# WS2812B_Single_Channel.net
KiCad netlist of a schematic drawn in Altium Designer
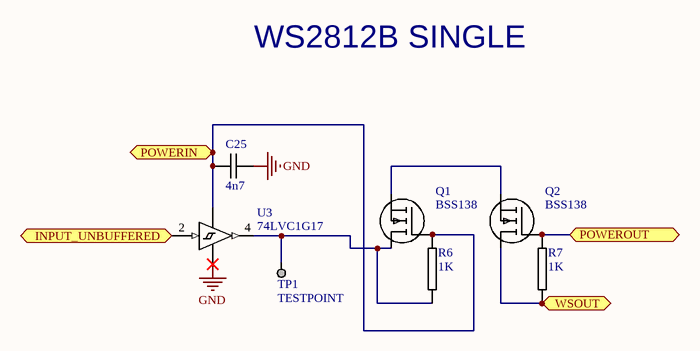
[diagram p0: WS2812B Single Channel.SchDoc]

(export (version "E")
  (design (tool "Eeschema 10.0.6"))
  (components
    (comp (ref "C25")
      (value "4n7")
      (footprint "0603C-TBD")
      (description "CAPACITOR 0603 CERAMIC")
      (libsource (lib "RVA_Altium_Library") (part "0603C-4N7"))
    )
    (comp (ref "Q1")
      (value "BSS138")
      (footprint "SOT23-GDS")
      (description "N CHANNEL MOSFET BSS138 SOT23")
      (fields
        (field (name "MANUFACTURER") "Fairchild Semiconductor")
        (field (name "MANUFACTURER PART NUMBER") "2N7002")
      )
      (libsource (lib "RVA_Altium_Library") (part "BSS138-SOT23"))
    )
    (comp (ref "Q2")
      (value "BSS138")
      (footprint "SOT23-GDS")
      (description "N CHANNEL MOSFET BSS138 SOT23")
      (fields
        (field (name "MANUFACTURER") "Fairchild Semiconductor")
        (field (name "MANUFACTURER PART NUMBER") "2N7002")
      )
      (libsource (lib "RVA_Altium_Library") (part "BSS138-SOT23"))
    )
    (comp (ref "R6")
      (value "1K")
      (footprint "0603R-1k")
      (description "GENERIC RESISTOR 0603")
      (fields
        (field (name "MANUFACTURER PART NUMBER") "RMCF 1/16 1K 1% R")
        (field (name "MANUFACTURER") "Stackpole Electronics Inc")
      )
      (libsource (lib "RVA_Altium_Library") (part "0603R-1K"))
    )
    (comp (ref "R7")
      (value "1K")
      (footprint "0603R-1k")
      (description "GENERIC RESISTOR 0603")
      (fields
        (field (name "MANUFACTURER PART NUMBER") "RMCF 1/16 1K 1% R")
        (field (name "MANUFACTURER") "Stackpole Electronics Inc")
      )
      (libsource (lib "RVA_Altium_Library") (part "0603R-1K"))
    )
    (comp (ref "TP1")
      (value "TESTPOINT")
      (footprint "TESTPOINT")
      (description "TESTPOINT SCOPE GRABBER")
      (fields
        (field (name "MANUFACTURER PART NUMBER") "5010")
        (field (name "MANUFACTURER") "Keystone Electronics")
      )
      (libsource (lib "vh_altium_library") (part "TESTPOINT"))
    )
    (comp (ref "U3")
      (value "74LVC1G17")
      (footprint "SOT-353")
      (description "Single buffer")
      (libsource (lib "RVA_Altium_Library") (part "74LVC1G17"))
    )
  )
  (nets
    (net (code "1") (name "/INPUT_UNBUFFERED") (class "Default")
      (node (ref "U3") (pin "2") (pinfunction "A_2") (pintype "input"))
    )
    (net (code "2") (name "/POWERIN") (class "Default")
      (node (ref "C25") (pin "1") (pintype "passive"))
      (node (ref "Q1") (pin "G") (pintype "passive"))
      (node (ref "R6") (pin "1") (pintype "passive"))
      (node (ref "U3") (pin "5") (pinfunction "VCC_5") (pintype "passive"))
    )
    (net (code "3") (name "/POWEROUT") (class "Default")
      (node (ref "Q2") (pin "G") (pintype "passive"))
      (node (ref "R7") (pin "1") (pintype "passive"))
    )
    (net (code "4") (name "/WSOUT") (class "Default")
      (node (ref "Q2") (pin "D") (pintype "passive"))
      (node (ref "R7") (pin "2") (pintype "passive"))
    )
    (net (code "5") (name "GND") (class "Default")
      (node (ref "C25") (pin "2") (pintype "passive"))
      (node (ref "U3") (pin "3") (pinfunction "GND_3") (pintype "power_in"))
    )
    (net (code "6") (name "Net-(Q1-PadS)") (class "Default")
      (node (ref "Q1") (pin "S") (pintype "passive"))
      (node (ref "Q2") (pin "S") (pintype "passive"))
    )
    (net (code "7") (name "Net-(U3-Y)") (class "Default")
      (node (ref "Q1") (pin "D") (pintype "passive"))
      (node (ref "R6") (pin "2") (pintype "passive"))
      (node (ref "TP1") (pin "1") (pinfunction "1_1") (pintype "passive"))
      (node (ref "U3") (pin "4") (pinfunction "Y_4") (pintype "output"))
    )
  )
)
